# 1_WIZ750SR_W7500P.net
KiCad netlist of a schematic drawn in Altium Designer
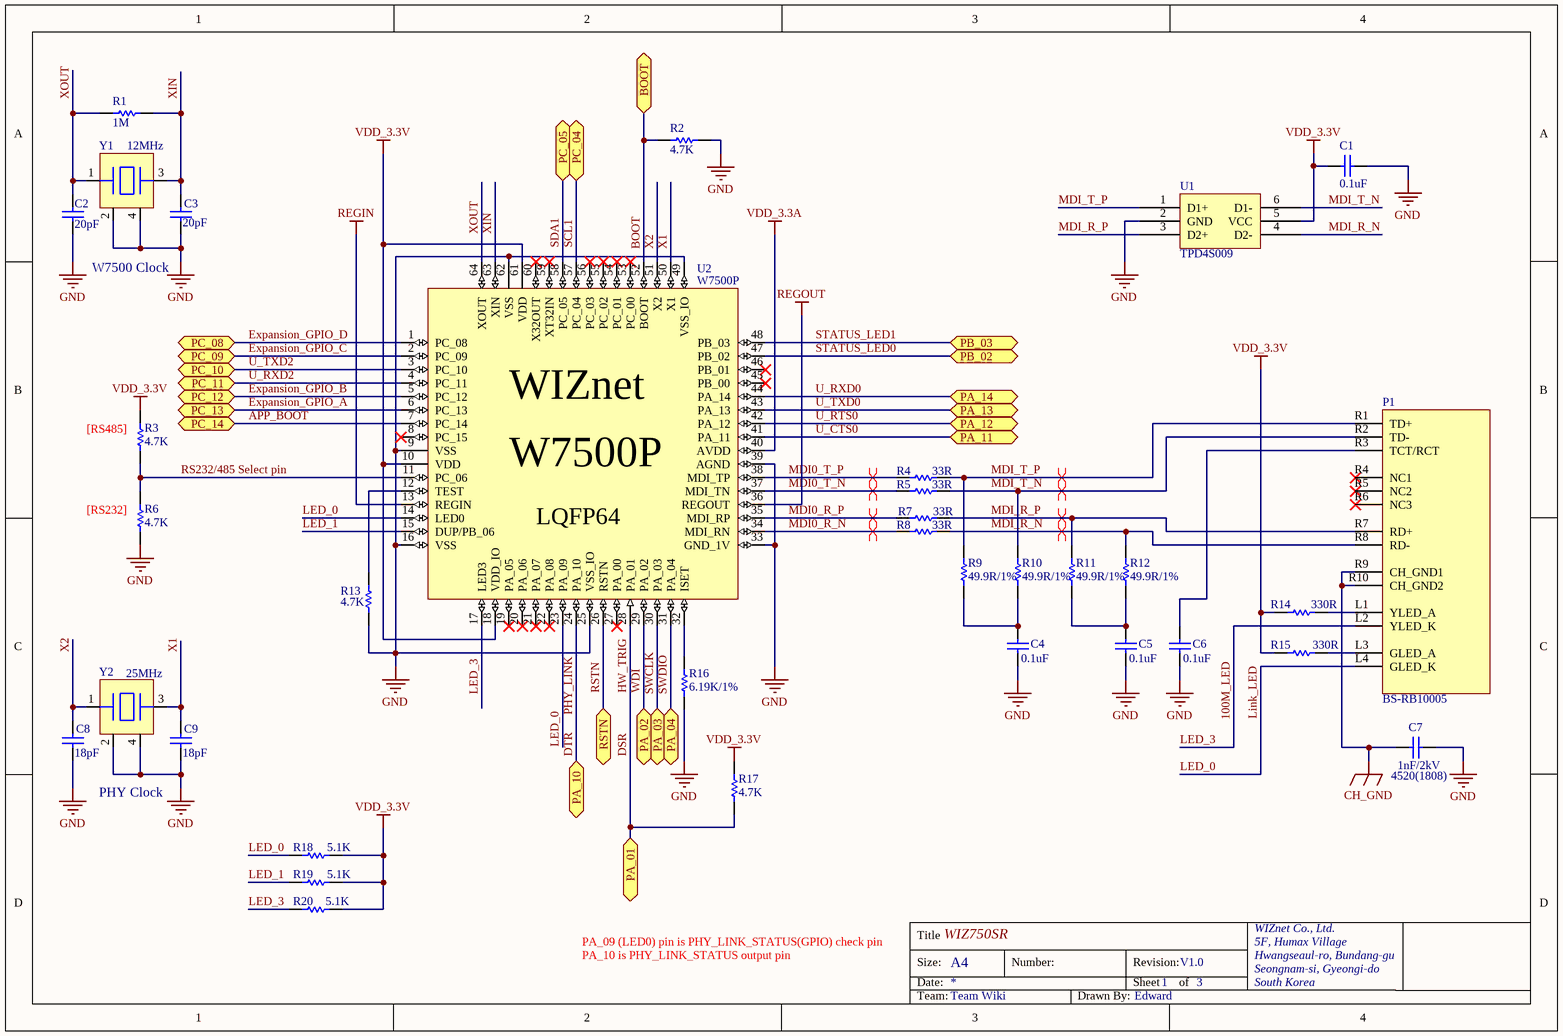
[diagram p0: 1.WIZ750SR_W7500P.SchDoc]

(export (version "E")
  (design (tool "Eeschema 10.0.6"))
  (components
    (comp (ref "C1")
      (value "0.1uF")
      (footprint "CAP-0402")
      (description "Ceramic CAP 0402(1005)")
      (libsource (lib "Scott_lib") (part "CAP-0402"))
    )
    (comp (ref "C2")
      (value "20pF")
      (footprint "CAP-0402")
      (description "Ceramic CAP 0402(1005)")
      (libsource (lib "Scott_lib") (part "CAP-0402"))
    )
    (comp (ref "C3")
      (value "20pF")
      (footprint "CAP-0402")
      (description "Ceramic CAP 0402(1005)")
      (libsource (lib "Scott_lib") (part "CAP-0402"))
    )
    (comp (ref "C4")
      (value "0.1uF")
      (footprint "CAP-0402")
      (description "Ceramic CAP 0402(1005)")
      (libsource (lib "Scott_lib") (part "CAP-0402"))
    )
    (comp (ref "C5")
      (value "0.1uF")
      (footprint "CAP-0402")
      (description "Ceramic CAP 0402(1005)")
      (libsource (lib "Scott_lib") (part "CAP-0402"))
    )
    (comp (ref "C6")
      (value "0.1uF")
      (footprint "CAP-0402")
      (description "Ceramic CAP 0402(1005)")
      (libsource (lib "Scott_lib") (part "CAP-0402"))
    )
    (comp (ref "C7")
      (value "1nF/2kV")
      (footprint "CAP-1808")
      (description "Ceramic CAP 1808(4520)")
      (libsource (lib "Scott_lib") (part "CAP-1808"))
    )
    (comp (ref "C8")
      (value "18pF")
      (footprint "CAP-0402")
      (description "Ceramic CAP 0402(1005)")
      (libsource (lib "Scott_lib") (part "CAP-0402"))
    )
    (comp (ref "C9")
      (value "18pF")
      (footprint "CAP-0402")
      (description "Ceramic CAP 0402(1005)")
      (libsource (lib "Scott_lib") (part "CAP-0402"))
    )
    (comp (ref "P1")
      (value "BS-RB10005")
      (footprint "RJ45-125BAG1A")
      (description "10/100 BASE-TX MAGJACK")
      (libsource (lib "Edward") (part "RB1-125BAG1A"))
    )
    (comp (ref "R1")
      (value "1M")
      (footprint "RES-0402")
      (description "RES-0402")
      (libsource (lib "Scott_lib") (part "RES-0402"))
    )
    (comp (ref "R2")
      (value "4.7K")
      (footprint "RES-0402")
      (description "RES-0402")
      (libsource (lib "Scott_lib") (part "RES-0402"))
    )
    (comp (ref "R3")
      (value "4.7K")
      (footprint "RES-0402")
      (description "RES-0402")
      (libsource (lib "Scott_lib") (part "RES-0402"))
    )
    (comp (ref "R4")
      (value "33R")
      (footprint "RES-0402")
      (description "RES-0402")
      (libsource (lib "Scott_lib") (part "RES-0402"))
    )
    (comp (ref "R5")
      (value "33R")
      (footprint "RES-0402")
      (description "RES-0402")
      (libsource (lib "Scott_lib") (part "RES-0402"))
    )
    (comp (ref "R6")
      (value "4.7K")
      (footprint "RES-0402")
      (description "RES-0402")
      (libsource (lib "Scott_lib") (part "RES-0402"))
    )
    (comp (ref "R7")
      (value "33R")
      (footprint "RES-0402")
      (description "RES-0402")
      (libsource (lib "Scott_lib") (part "RES-0402"))
    )
    (comp (ref "R8")
      (value "33R")
      (footprint "RES-0402")
      (description "RES-0402")
      (libsource (lib "Scott_lib") (part "RES-0402"))
    )
    (comp (ref "R9")
      (value "49.9R/1%")
      (footprint "RES-0402")
      (description "RES-0402")
      (libsource (lib "Scott_lib") (part "RES-0402"))
    )
    (comp (ref "R10")
      (value "49.9R/1%")
      (footprint "RES-0402")
      (description "RES-0402")
      (libsource (lib "Scott_lib") (part "RES-0402"))
    )
    (comp (ref "R11")
      (value "49.9R/1%")
      (footprint "RES-0402")
      (description "RES-0402")
      (libsource (lib "Scott_lib") (part "RES-0402"))
    )
    (comp (ref "R12")
      (value "49.9R/1%")
      (footprint "RES-0402")
      (description "RES-0402")
      (libsource (lib "Scott_lib") (part "RES-0402"))
    )
    (comp (ref "R13")
      (value "4.7K")
      (footprint "RES-0402")
      (description "RES-0402")
      (libsource (lib "Scott_lib") (part "RES-0402"))
    )
    (comp (ref "R14")
      (value "330R")
      (footprint "RES-0402")
      (description "RES-0402")
      (libsource (lib "Scott_lib") (part "RES-0402"))
    )
    (comp (ref "R15")
      (value "330R")
      (footprint "RES-0402")
      (description "RES-0402")
      (libsource (lib "Scott_lib") (part "RES-0402"))
    )
    (comp (ref "R16")
      (value "6.19K/1%")
      (footprint "RES-0402")
      (description "RES-0402")
      (libsource (lib "Scott_lib") (part "RES-0402"))
    )
    (comp (ref "R17")
      (value "4.7K")
      (footprint "RES-0402")
      (description "RES-0402")
      (libsource (lib "Scott_lib") (part "RES-0402"))
    )
    (comp (ref "R18")
      (value "5.1K")
      (footprint "RES-0402")
      (description "RES-0402")
      (libsource (lib "Scott_lib") (part "RES-0402"))
    )
    (comp (ref "R19")
      (value "5.1K")
      (footprint "RES-0402")
      (description "RES-0402")
      (libsource (lib "Scott_lib") (part "RES-0402"))
    )
    (comp (ref "R20")
      (value "5.1K")
      (footprint "RES-0402")
      (description "RES-0402")
      (libsource (lib "Scott_lib") (part "RES-0402"))
    )
    (comp (ref "U1")
      (value "TPD4S009")
      (footprint "SOT-23-6L")
      (description "6-PIN SOT DBVor DCK Package")
      (libsource (lib "tpd4s009_SOT") (part "tpd4s009"))
    )
    (comp (ref "U2")
      (value "W7500P")
      (footprint "W7500-LQFP64")
      (description "WIZnet ARM Cortex-M0, Add PHY")
      (libsource (lib "Scott_lib") (part "W7500P"))
    )
    (comp (ref "Y1")
      (value "12MHz")
      (footprint "OSC-TZ1067B")
      (description "X-tal 12MHz,3.2x2.5 SMD, CL=20pF")
      (libsource (lib "Scott_lib") (part "OSC-TZ1067B-12MHz"))
    )
    (comp (ref "Y2")
      (value "25MHz")
      (footprint "OSC-82J0626")
      (description "X-tal 25MHz,3.2x2.5 SMD, CL=18pF")
      (libsource (lib "Scott_lib") (part "OSC-82J0626-25MHz"))
    )
  )
  (nets
    (net (code "1") (name "/100M_LED") (class "Default")
      (node (ref "P1") (pin "L2") (pinfunction "YLED_K_L2") (pintype "passive"))
      (node (ref "R20") (pin "1") (pinfunction "1_1") (pintype "passive"))
      (node (ref "U2") (pin "17") (pinfunction "LED3_17") (pintype "bidirectional"))
    )
    (net (code "2") (name "/APP_BOOT") (class "Default")
      (node (ref "U2") (pin "7") (pinfunction "PC_14_7") (pintype "bidirectional"))
    )
    (net (code "3") (name "/BOOT") (class "Default")
      (node (ref "R2") (pin "2") (pinfunction "2_2") (pintype "passive"))
      (node (ref "U2") (pin "52") (pinfunction "BOOT_52") (pintype "bidirectional"))
    )
    (net (code "4") (name "/DSR") (class "Default")
      (node (ref "R17") (pin "2") (pinfunction "2_2") (pintype "passive"))
      (node (ref "U2") (pin "28") (pinfunction "PA_01_28") (pintype "input"))
    )
    (net (code "5") (name "/DTR") (class "Default")
      (node (ref "U2") (pin "24") (pinfunction "PA_10_24") (pintype "bidirectional"))
    )
    (net (code "6") (name "/Expansion_GPIO_A") (class "Default")
      (node (ref "U2") (pin "6") (pinfunction "PC_13_6") (pintype "bidirectional"))
    )
    (net (code "7") (name "/Expansion_GPIO_B") (class "Default")
      (node (ref "U2") (pin "5") (pinfunction "PC_12_5") (pintype "bidirectional"))
    )
    (net (code "8") (name "/Expansion_GPIO_C") (class "Default")
      (node (ref "U2") (pin "2") (pinfunction "PC_09_2") (pintype "bidirectional"))
    )
    (net (code "9") (name "/Expansion_GPIO_D") (class "Default")
      (node (ref "U2") (pin "1") (pinfunction "PC_08_1") (pintype "bidirectional"))
    )
    (net (code "10") (name "/LED_0") (class "Default")
      (node (ref "P1") (pin "L4") (pinfunction "GLED_K_L4") (pintype "passive"))
      (node (ref "R18") (pin "1") (pinfunction "1_1") (pintype "passive"))
      (node (ref "U2") (pin "14") (pinfunction "LED0_14") (pintype "bidirectional"))
      (node (ref "U2") (pin "23") (pinfunction "PA_09_23") (pintype "bidirectional"))
    )
    (net (code "11") (name "/LED_1") (class "Default")
      (node (ref "R19") (pin "1") (pinfunction "1_1") (pintype "passive"))
      (node (ref "U2") (pin "15") (pinfunction "DUP/PB_06_15") (pintype "bidirectional"))
    )
    (net (code "12") (name "/MDI0_R_N") (class "Default")
      (node (ref "R8") (pin "1") (pinfunction "1_1") (pintype "passive"))
      (node (ref "U2") (pin "34") (pinfunction "MDI_RN_34") (pintype "bidirectional"))
    )
    (net (code "13") (name "/MDI0_R_P") (class "Default")
      (node (ref "R7") (pin "1") (pinfunction "1_1") (pintype "passive"))
      (node (ref "U2") (pin "35") (pinfunction "MDI_RP_35") (pintype "bidirectional"))
    )
    (net (code "14") (name "/MDI0_T_N") (class "Default")
      (node (ref "R5") (pin "1") (pinfunction "1_1") (pintype "passive"))
      (node (ref "U2") (pin "37") (pinfunction "MDI_TN_37") (pintype "bidirectional"))
    )
    (net (code "15") (name "/MDI0_T_P") (class "Default")
      (node (ref "R4") (pin "1") (pinfunction "1_1") (pintype "passive"))
      (node (ref "U2") (pin "38") (pinfunction "MDI_TP_38") (pintype "bidirectional"))
    )
    (net (code "16") (name "/MDI_R_N") (class "Default")
      (node (ref "P1") (pin "R8") (pinfunction "RD-_R8") (pintype "passive"))
      (node (ref "R12") (pin "2") (pinfunction "2_2") (pintype "passive"))
      (node (ref "R8") (pin "2") (pinfunction "2_2") (pintype "passive"))
      (node (ref "U1") (pin "4") (pinfunction "D2-_4") (pintype "passive"))
    )
    (net (code "17") (name "/MDI_R_P") (class "Default")
      (node (ref "P1") (pin "R7") (pinfunction "RD+_R7") (pintype "passive"))
      (node (ref "R11") (pin "2") (pinfunction "2_2") (pintype "passive"))
      (node (ref "R7") (pin "2") (pinfunction "2_2") (pintype "passive"))
      (node (ref "U1") (pin "3") (pinfunction "D2+_3") (pintype "passive"))
    )
    (net (code "18") (name "/MDI_T_N") (class "Default")
      (node (ref "P1") (pin "R2") (pinfunction "TD-_R2") (pintype "passive"))
      (node (ref "R10") (pin "2") (pinfunction "2_2") (pintype "passive"))
      (node (ref "R5") (pin "2") (pinfunction "2_2") (pintype "passive"))
      (node (ref "U1") (pin "6") (pinfunction "D1-_6") (pintype "passive"))
    )
    (net (code "19") (name "/MDI_T_P") (class "Default")
      (node (ref "P1") (pin "R1") (pinfunction "TD+_R1") (pintype "passive"))
      (node (ref "R4") (pin "2") (pinfunction "2_2") (pintype "passive"))
      (node (ref "R9") (pin "2") (pinfunction "2_2") (pintype "passive"))
      (node (ref "U1") (pin "1") (pinfunction "D1+_1") (pintype "passive"))
    )
    (net (code "20") (name "/RS232{slash}485 Select pin") (class "Default")
      (node (ref "R3") (pin "1") (pinfunction "1_1") (pintype "passive"))
      (node (ref "R6") (pin "2") (pinfunction "2_2") (pintype "passive"))
      (node (ref "U2") (pin "11") (pinfunction "PC_06_11") (pintype "bidirectional"))
    )
    (net (code "21") (name "/RSTN") (class "Default")
      (node (ref "U2") (pin "26") (pinfunction "RSTN_26") (pintype "bidirectional"))
    )
    (net (code "22") (name "/SCL1") (class "Default")
      (node (ref "U2") (pin "57") (pinfunction "PC_04_57") (pintype "bidirectional"))
    )
    (net (code "23") (name "/SDA1") (class "Default")
      (node (ref "U2") (pin "58") (pinfunction "PC_05_58") (pintype "bidirectional"))
    )
    (net (code "24") (name "/STATUS_LED0") (class "Default")
      (node (ref "U2") (pin "47") (pinfunction "PB_02_47") (pintype "bidirectional"))
    )
    (net (code "25") (name "/STATUS_LED1") (class "Default")
      (node (ref "U2") (pin "48") (pinfunction "PB_03_48") (pintype "bidirectional"))
    )
    (net (code "26") (name "/SWCLK") (class "Default")
      (node (ref "U2") (pin "30") (pinfunction "PA_03_30") (pintype "bidirectional"))
    )
    (net (code "27") (name "/SWDIO") (class "Default")
      (node (ref "U2") (pin "31") (pinfunction "PA_04_31") (pintype "bidirectional"))
    )
    (net (code "28") (name "/U_CTS0") (class "Default")
      (node (ref "U2") (pin "41") (pinfunction "PA_11_41") (pintype "bidirectional"))
    )
    (net (code "29") (name "/U_RTS0") (class "Default")
      (node (ref "U2") (pin "42") (pinfunction "PA_12_42") (pintype "bidirectional"))
    )
    (net (code "30") (name "/U_RXD0") (class "Default")
      (node (ref "U2") (pin "44") (pinfunction "PA_14_44") (pintype "bidirectional"))
    )
    (net (code "31") (name "/U_RXD2") (class "Default")
      (node (ref "U2") (pin "4") (pinfunction "PC_11_4") (pintype "bidirectional"))
    )
    (net (code "32") (name "/U_TXD0") (class "Default")
      (node (ref "U2") (pin "43") (pinfunction "PA_13_43") (pintype "bidirectional"))
    )
    (net (code "33") (name "/U_TXD2") (class "Default")
      (node (ref "U2") (pin "3") (pinfunction "PC_10_3") (pintype "bidirectional"))
    )
    (net (code "34") (name "/WDI") (class "Default")
      (node (ref "U2") (pin "29") (pinfunction "PA_02_29") (pintype "bidirectional"))
    )
    (net (code "35") (name "/X1") (class "Default")
      (node (ref "C9") (pin "2") (pinfunction "2_2") (pintype "passive"))
      (node (ref "U2") (pin "50") (pinfunction "X1_50") (pintype "bidirectional"))
      (node (ref "Y2") (pin "3") (pinfunction "3_3") (pintype "passive"))
    )
    (net (code "36") (name "/X2") (class "Default")
      (node (ref "C8") (pin "2") (pinfunction "2_2") (pintype "passive"))
      (node (ref "U2") (pin "51") (pinfunction "X2_51") (pintype "bidirectional"))
      (node (ref "Y2") (pin "1") (pinfunction "1_1") (pintype "passive"))
    )
    (net (code "37") (name "/XIN") (class "Default")
      (node (ref "C3") (pin "2") (pinfunction "2_2") (pintype "passive"))
      (node (ref "R1") (pin "2") (pinfunction "2_2") (pintype "passive"))
      (node (ref "U2") (pin "63") (pinfunction "XIN_63") (pintype "bidirectional"))
      (node (ref "Y1") (pin "3") (pinfunction "3_3") (pintype "passive"))
    )
    (net (code "38") (name "/XOUT") (class "Default")
      (node (ref "C2") (pin "2") (pinfunction "2_2") (pintype "passive"))
      (node (ref "R1") (pin "1") (pinfunction "1_1") (pintype "passive"))
      (node (ref "U2") (pin "64") (pinfunction "XOUT_64") (pintype "bidirectional"))
      (node (ref "Y1") (pin "1") (pinfunction "1_1") (pintype "passive"))
    )
    (net (code "39") (name "CH_GND") (class "Default")
      (node (ref "C7") (pin "2") (pinfunction "2_2") (pintype "passive"))
      (node (ref "P1") (pin "R10") (pinfunction "CH_GND2_R10") (pintype "passive"))
      (node (ref "P1") (pin "R9") (pinfunction "CH_GND1_R9") (pintype "passive"))
    )
    (net (code "40") (name "GND") (class "Default")
      (node (ref "C1") (pin "1") (pinfunction "1_1") (pintype "passive"))
      (node (ref "C2") (pin "1") (pinfunction "1_1") (pintype "passive"))
      (node (ref "C3") (pin "1") (pinfunction "1_1") (pintype "passive"))
      (node (ref "C4") (pin "1") (pinfunction "1_1") (pintype "passive"))
      (node (ref "C5") (pin "1") (pinfunction "1_1") (pintype "passive"))
      (node (ref "C6") (pin "1") (pinfunction "1_1") (pintype "passive"))
      (node (ref "C7") (pin "1") (pinfunction "1_1") (pintype "passive"))
      (node (ref "C8") (pin "1") (pinfunction "1_1") (pintype "passive"))
      (node (ref "C9") (pin "1") (pinfunction "1_1") (pintype "passive"))
      (node (ref "R13") (pin "1") (pinfunction "1_1") (pintype "passive"))
      (node (ref "R16") (pin "1") (pinfunction "1_1") (pintype "passive"))
      (node (ref "R2") (pin "1") (pinfunction "1_1") (pintype "passive"))
      (node (ref "R6") (pin "1") (pinfunction "1_1") (pintype "passive"))
      (node (ref "U1") (pin "2") (pinfunction "GND_2") (pintype "passive"))
      (node (ref "U2") (pin "16") (pinfunction "VSS_16") (pintype "bidirectional"))
      (node (ref "U2") (pin "25") (pinfunction "VSS_IO_25") (pintype "bidirectional"))
      (node (ref "U2") (pin "33") (pinfunction "GND_1V_33") (pintype "bidirectional"))
      (node (ref "U2") (pin "39") (pinfunction "AGND_39") (pintype "bidirectional"))
      (node (ref "U2") (pin "49") (pinfunction "VSS_IO_49") (pintype "bidirectional"))
      (node (ref "U2") (pin "62") (pinfunction "VSS_62") (pintype "power_in"))
      (node (ref "U2") (pin "9") (pinfunction "VSS_9") (pintype "power_in"))
      (node (ref "Y1") (pin "2") (pinfunction "2_2") (pintype "passive"))
      (node (ref "Y1") (pin "4") (pinfunction "4_4") (pintype "passive"))
      (node (ref "Y2") (pin "2") (pinfunction "2_2") (pintype "passive"))
      (node (ref "Y2") (pin "4") (pinfunction "4_4") (pintype "passive"))
    )
    (net (code "41") (name "Net-(C4-Pad2)") (class "Default")
      (node (ref "C4") (pin "2") (pinfunction "2_2") (pintype "passive"))
      (node (ref "R10") (pin "1") (pinfunction "1_1") (pintype "passive"))
      (node (ref "R9") (pin "1") (pinfunction "1_1") (pintype "passive"))
    )
    (net (code "42") (name "Net-(C5-Pad2)") (class "Default")
      (node (ref "C5") (pin "2") (pinfunction "2_2") (pintype "passive"))
      (node (ref "R11") (pin "1") (pinfunction "1_1") (pintype "passive"))
      (node (ref "R12") (pin "1") (pinfunction "1_1") (pintype "passive"))
    )
    (net (code "43") (name "Net-(P1-GLED_A)") (class "Default")
      (node (ref "P1") (pin "L3") (pinfunction "GLED_A_L3") (pintype "passive"))
      (node (ref "R15") (pin "2") (pinfunction "2_2") (pintype "passive"))
    )
    (net (code "44") (name "Net-(P1-TCT{slash}RCT)") (class "Default")
      (node (ref "C6") (pin "2") (pinfunction "2_2") (pintype "passive"))
      (node (ref "P1") (pin "R3") (pinfunction "TCT/RCT_R3") (pintype "passive"))
    )
    (net (code "45") (name "Net-(P1-YLED_A)") (class "Default")
      (node (ref "P1") (pin "L1") (pinfunction "YLED_A_L1") (pintype "passive"))
      (node (ref "R14") (pin "2") (pinfunction "2_2") (pintype "passive"))
    )
    (net (code "46") (name "Net-(U2-ISET)") (class "Default")
      (node (ref "R16") (pin "2") (pinfunction "2_2") (pintype "passive"))
      (node (ref "U2") (pin "32") (pinfunction "ISET_32") (pintype "bidirectional"))
    )
    (net (code "47") (name "Net-(U2-TEST)") (class "Default")
      (node (ref "R13") (pin "2") (pinfunction "2_2") (pintype "passive"))
      (node (ref "U2") (pin "12") (pinfunction "TEST_12") (pintype "bidirectional"))
    )
    (net (code "48") (name "REGIN") (class "Default")
      (node (ref "U2") (pin "13") (pinfunction "REGIN_13") (pintype "bidirectional"))
    )
    (net (code "49") (name "REGOUT") (class "Default")
      (node (ref "U2") (pin "36") (pinfunction "REGOUT_36") (pintype "bidirectional"))
    )
    (net (code "50") (name "VDD_3.3A") (class "Default")
      (node (ref "U2") (pin "40") (pinfunction "AVDD_40") (pintype "bidirectional"))
    )
    (net (code "51") (name "VDD_3.3V") (class "Default")
      (node (ref "C1") (pin "2") (pinfunction "2_2") (pintype "passive"))
      (node (ref "R14") (pin "1") (pinfunction "1_1") (pintype "passive"))
      (node (ref "R15") (pin "1") (pinfunction "1_1") (pintype "passive"))
      (node (ref "R17") (pin "1") (pinfunction "1_1") (pintype "passive"))
      (node (ref "R18") (pin "2") (pinfunction "2_2") (pintype "passive"))
      (node (ref "R19") (pin "2") (pinfunction "2_2") (pintype "passive"))
      (node (ref "R20") (pin "2") (pinfunction "2_2") (pintype "passive"))
      (node (ref "R3") (pin "2") (pinfunction "2_2") (pintype "passive"))
      (node (ref "U1") (pin "5") (pinfunction "VCC_5") (pintype "passive"))
      (node (ref "U2") (pin "10") (pinfunction "VDD_10") (pintype "power_in"))
      (node (ref "U2") (pin "18") (pinfunction "VDD_IO_18") (pintype "bidirectional"))
      (node (ref "U2") (pin "61") (pinfunction "VDD_61") (pintype "power_in"))
    )
    (net (code "52") (name "unconnected-(P1-NC1-PadR4)") (class "Default")
      (node (ref "P1") (pin "R4") (pinfunction "NC1_R4") (pintype "passive+no_connect"))
    )
    (net (code "53") (name "unconnected-(P1-NC2-PadR5)") (class "Default")
      (node (ref "P1") (pin "R5") (pinfunction "NC2_R5") (pintype "passive+no_connect"))
    )
    (net (code "54") (name "unconnected-(P1-NC3-PadR6)") (class "Default")
      (node (ref "P1") (pin "R6") (pinfunction "NC3_R6") (pintype "passive+no_connect"))
    )
    (net (code "55") (name "unconnected-(U2-PA_00-Pad27)") (class "Default")
      (node (ref "U2") (pin "27") (pinfunction "PA_00_27") (pintype "bidirectional+no_connect"))
    )
    (net (code "56") (name "unconnected-(U2-PA_05-Pad19)") (class "Default")
      (node (ref "U2") (pin "19") (pinfunction "PA_05_19") (pintype "bidirectional+no_connect"))
    )
    (net (code "57") (name "unconnected-(U2-PA_06-Pad20)") (class "Default")
      (node (ref "U2") (pin "20") (pinfunction "PA_06_20") (pintype "bidirectional+no_connect"))
    )
    (net (code "58") (name "unconnected-(U2-PA_07-Pad21)") (class "Default")
      (node (ref "U2") (pin "21") (pinfunction "PA_07_21") (pintype "bidirectional+no_connect"))
    )
    (net (code "59") (name "unconnected-(U2-PA_08-Pad22)") (class "Default")
      (node (ref "U2") (pin "22") (pinfunction "PA_08_22") (pintype "bidirectional+no_connect"))
    )
    (net (code "60") (name "unconnected-(U2-PB_00-Pad45)") (class "Default")
      (node (ref "U2") (pin "45") (pinfunction "PB_00_45") (pintype "bidirectional+no_connect"))
    )
    (net (code "61") (name "unconnected-(U2-PB_01-Pad46)") (class "Default")
      (node (ref "U2") (pin "46") (pinfunction "PB_01_46") (pintype "bidirectional+no_connect"))
    )
    (net (code "62") (name "unconnected-(U2-PC_00-Pad53)") (class "Default")
      (node (ref "U2") (pin "53") (pinfunction "PC_00_53") (pintype "bidirectional+no_connect"))
    )
    (net (code "63") (name "unconnected-(U2-PC_01-Pad54)") (class "Default")
      (node (ref "U2") (pin "54") (pinfunction "PC_01_54") (pintype "bidirectional+no_connect"))
    )
    (net (code "64") (name "unconnected-(U2-PC_02-Pad55)") (class "Default")
      (node (ref "U2") (pin "55") (pinfunction "PC_02_55") (pintype "bidirectional+no_connect"))
    )
    (net (code "65") (name "unconnected-(U2-PC_03-Pad56)") (class "Default")
      (node (ref "U2") (pin "56") (pinfunction "PC_03_56") (pintype "bidirectional+no_connect"))
    )
    (net (code "66") (name "unconnected-(U2-PC_15-Pad8)") (class "Default")
      (node (ref "U2") (pin "8") (pinfunction "PC_15_8") (pintype "bidirectional+no_connect"))
    )
    (net (code "67") (name "unconnected-(U2-X32OUT-Pad60)") (class "Default")
      (node (ref "U2") (pin "60") (pinfunction "X32OUT_60") (pintype "bidirectional+no_connect"))
    )
    (net (code "68") (name "unconnected-(U2-XT32IN-Pad59)") (class "Default")
      (node (ref "U2") (pin "59") (pinfunction "XT32IN_59") (pintype "bidirectional+no_connect"))
    )
  )
)
